# Tally_v03.net
KiCad netlist of a schematic drawn in EAGLE
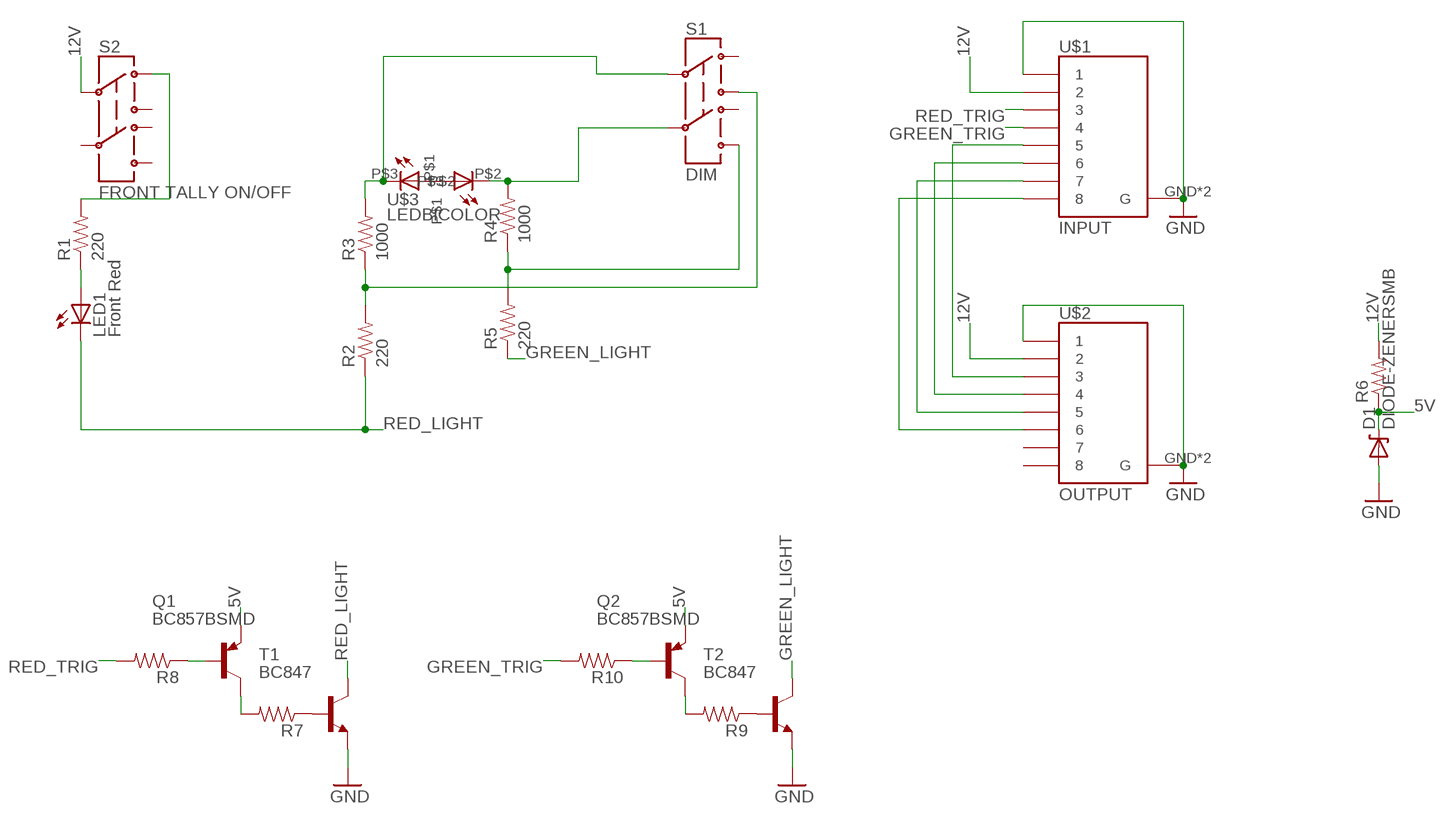
[diagram p0: schematic, sheet 1]

(export (version "E")
  (design (tool "Eeschema 10.0.6"))
  (components
    (comp (ref "D1")
      (value "DIODE-ZENERSMB")
      (footprint "eagle-import:SMB-DIODE")
      (libsource (lib "eagle-import") (part "DIODE-ZENERSMB"))
    )
    (comp (ref "LED1")
      (value "Front Red")
      (footprint "eagle-import:LED20")
      (libsource (lib "eagle-import") (part "LED20"))
    )
    (comp (ref "Q1")
      (value "BC857BSMD")
      (footprint "eagle-import:SOT23-BEC")
      (libsource (lib "eagle-import") (part "BC857SMDB"))
    )
    (comp (ref "Q2")
      (value "BC857BSMD")
      (footprint "eagle-import:SOT23-BEC")
      (libsource (lib "eagle-import") (part "BC857SMDB"))
    )
    (comp (ref "R1")
      (value "220")
      (footprint "eagle-import:0603-RES")
      (libsource (lib "eagle-import") (part "RESISTOR0603-RES"))
    )
    (comp (ref "R2")
      (value "220")
      (footprint "eagle-import:0603-RES")
      (libsource (lib "eagle-import") (part "RESISTOR0603-RES"))
    )
    (comp (ref "R3")
      (value "1000")
      (footprint "eagle-import:0603-RES")
      (libsource (lib "eagle-import") (part "RESISTOR0603-RES"))
    )
    (comp (ref "R4")
      (value "1000")
      (footprint "eagle-import:0603-RES")
      (libsource (lib "eagle-import") (part "RESISTOR0603-RES"))
    )
    (comp (ref "R5")
      (value "220")
      (footprint "eagle-import:0603-RES")
      (libsource (lib "eagle-import") (part "RESISTOR0603-RES"))
    )
    (comp (ref "R6")
      (value "RESISTOR0603-RES")
      (footprint "eagle-import:0603-RES")
      (libsource (lib "eagle-import") (part "RESISTOR0603-RES"))
    )
    (comp (ref "R7")
      (value "RESISTOR0603-RES")
      (footprint "eagle-import:0603-RES")
      (libsource (lib "eagle-import") (part "RESISTOR0603-RES"))
    )
    (comp (ref "R8")
      (value "RESISTOR0603-RES")
      (footprint "eagle-import:0603-RES")
      (libsource (lib "eagle-import") (part "RESISTOR0603-RES"))
    )
    (comp (ref "R9")
      (value "RESISTOR0603-RES")
      (footprint "eagle-import:0603-RES")
      (libsource (lib "eagle-import") (part "RESISTOR0603-RES"))
    )
    (comp (ref "R10")
      (value "RESISTOR0603-RES")
      (footprint "eagle-import:0603-RES")
      (libsource (lib "eagle-import") (part "RESISTOR0603-RES"))
    )
    (comp (ref "S1")
      (value "DIM")
      (footprint "eagle-import:TECONNECTIVITY-DPDT")
      (libsource (lib "eagle-import") (part "SWITCH-DPDTPTH1"))
    )
    (comp (ref "S2")
      (value "FRONT TALLY ON/OFF")
      (footprint "eagle-import:TECONNECTIVITY-DPDT")
      (libsource (lib "eagle-import") (part "SWITCH-DPDTPTH1"))
    )
    (comp (ref "T1")
      (value "BC847")
      (footprint "eagle-import:SOT23")
      (libsource (lib "eagle-import") (part "BC847"))
    )
    (comp (ref "T2")
      (value "BC847")
      (footprint "eagle-import:SOT23")
      (libsource (lib "eagle-import") (part "BC847"))
    )
    (comp (ref "U$1")
      (value "INPUT")
      (footprint "eagle-import:RJ45-8_GND")
      (libsource (lib "eagle-import") (part "RJ45-8_GND"))
    )
    (comp (ref "U$2")
      (value "OUTPUT")
      (footprint "eagle-import:RJ45-8_GND")
      (libsource (lib "eagle-import") (part "RJ45-8_GND"))
    )
    (comp (ref "U$3")
      (value "LEDBICOLOR")
      (footprint "eagle-import:LEDBICOLOR")
      (libsource (lib "eagle-import") (part "LEDBICOLOR"))
    )
  )
  (nets
    (net (code "1") (name "/5V") (class "Default")
      (node (ref "D1") (pin "C") (pinfunction "C_C") (pintype "passive"))
      (node (ref "Q1") (pin "E") (pinfunction "E_E") (pintype "passive"))
      (node (ref "Q2") (pin "E") (pinfunction "E_E") (pintype "passive"))
      (node (ref "R6") (pin "1") (pinfunction "1_1") (pintype "passive"))
    )
    (net (code "2") (name "/12V") (class "Default")
      (node (ref "R6") (pin "2") (pinfunction "2_2") (pintype "passive"))
      (node (ref "S2") (pin "P$2") (pinfunction "2_P$2") (pintype "bidirectional"))
      (node (ref "U$1") (pin "2") (pinfunction "2_2") (pintype "bidirectional"))
      (node (ref "U$2") (pin "2") (pinfunction "2_2") (pintype "bidirectional"))
    )
    (net (code "3") (name "/GREEN_LIGHT") (class "Default")
      (node (ref "R5") (pin "1") (pinfunction "1_1") (pintype "passive"))
      (node (ref "T2") (pin "3") (pinfunction "C_3") (pintype "passive"))
    )
    (net (code "4") (name "/GREEN_TRIG") (class "Default")
      (node (ref "R10") (pin "2") (pinfunction "2_2") (pintype "passive"))
      (node (ref "U$1") (pin "4") (pinfunction "4_4") (pintype "bidirectional"))
    )
    (net (code "5") (name "/RED_LIGHT") (class "Default")
      (node (ref "LED1") (pin "P$2") (pinfunction "C_P$2") (pintype "passive"))
      (node (ref "R2") (pin "1") (pinfunction "1_1") (pintype "passive"))
      (node (ref "T1") (pin "3") (pinfunction "C_3") (pintype "passive"))
    )
    (net (code "6") (name "/RED_TRIG") (class "Default")
      (node (ref "R8") (pin "2") (pinfunction "2_2") (pintype "passive"))
      (node (ref "U$1") (pin "3") (pinfunction "3_3") (pintype "bidirectional"))
    )
    (net (code "7") (name "GND") (class "Default")
      (node (ref "D1") (pin "A") (pinfunction "A_A") (pintype "passive"))
      (node (ref "T1") (pin "2") (pinfunction "E_2") (pintype "passive"))
      (node (ref "T2") (pin "2") (pinfunction "E_2") (pintype "passive"))
      (node (ref "U$1") (pin "1") (pinfunction "1_1") (pintype "bidirectional"))
      (node (ref "U$1") (pin "GND") (pinfunction "G_GND") (pintype "power_in"))
      (node (ref "U$1") (pin "GND1") (pinfunction "G_GND1") (pintype "power_in"))
      (node (ref "U$2") (pin "1") (pinfunction "1_1") (pintype "bidirectional"))
      (node (ref "U$2") (pin "GND") (pinfunction "G_GND") (pintype "power_in"))
      (node (ref "U$2") (pin "GND1") (pinfunction "G_GND1") (pintype "power_in"))
    )
    (net (code "8") (name "Net-(LED1-A)") (class "Default")
      (node (ref "LED1") (pin "P$1") (pinfunction "A_P$1") (pintype "passive"))
      (node (ref "R1") (pin "1") (pinfunction "1_1") (pintype "passive"))
    )
    (net (code "9") (name "Net-(Q1-PadB)") (class "Default")
      (node (ref "Q1") (pin "B") (pinfunction "B_B") (pintype "passive"))
      (node (ref "R8") (pin "1") (pinfunction "1_1") (pintype "passive"))
    )
    (net (code "10") (name "Net-(Q1-PadC)") (class "Default")
      (node (ref "Q1") (pin "C") (pinfunction "C_C") (pintype "passive"))
      (node (ref "R7") (pin "2") (pinfunction "2_2") (pintype "passive"))
    )
    (net (code "11") (name "Net-(Q2-PadB)") (class "Default")
      (node (ref "Q2") (pin "B") (pinfunction "B_B") (pintype "passive"))
      (node (ref "R10") (pin "1") (pinfunction "1_1") (pintype "passive"))
    )
    (net (code "12") (name "Net-(Q2-PadC)") (class "Default")
      (node (ref "Q2") (pin "C") (pinfunction "C_C") (pintype "passive"))
      (node (ref "R9") (pin "2") (pinfunction "2_2") (pintype "passive"))
    )
    (net (code "13") (name "Net-(S1-2)") (class "Default")
      (node (ref "R3") (pin "2") (pinfunction "2_2") (pintype "passive"))
      (node (ref "S1") (pin "P$2") (pinfunction "2_P$2") (pintype "bidirectional"))
      (node (ref "U$3") (pin "P$3") (pinfunction "P$3_P$3") (pintype "bidirectional"))
    )
    (net (code "14") (name "Net-(S1-3)") (class "Default")
      (node (ref "R2") (pin "2") (pinfunction "2_2") (pintype "passive"))
      (node (ref "R3") (pin "1") (pinfunction "1_1") (pintype "passive"))
      (node (ref "S1") (pin "P$3") (pinfunction "3_P$3") (pintype "bidirectional"))
    )
    (net (code "15") (name "Net-(S1-5)") (class "Default")
      (node (ref "R4") (pin "2") (pinfunction "2_2") (pintype "passive"))
      (node (ref "S1") (pin "P$5") (pinfunction "5_P$5") (pintype "bidirectional"))
      (node (ref "U$3") (pin "P$2") (pinfunction "P$2_P$2") (pintype "bidirectional"))
    )
    (net (code "16") (name "Net-(S1-6)") (class "Default")
      (node (ref "R4") (pin "1") (pinfunction "1_1") (pintype "passive"))
      (node (ref "R5") (pin "2") (pinfunction "2_2") (pintype "passive"))
      (node (ref "S1") (pin "P$6") (pinfunction "6_P$6") (pintype "bidirectional"))
    )
    (net (code "17") (name "Net-(S2-1)") (class "Default")
      (node (ref "R1") (pin "2") (pinfunction "2_2") (pintype "passive"))
      (node (ref "S2") (pin "P$1") (pinfunction "1_P$1") (pintype "bidirectional"))
    )
    (net (code "18") (name "Net-(T1-B)") (class "Default")
      (node (ref "R7") (pin "1") (pinfunction "1_1") (pintype "passive"))
      (node (ref "T1") (pin "1") (pinfunction "B_1") (pintype "passive"))
    )
    (net (code "19") (name "Net-(T2-B)") (class "Default")
      (node (ref "R9") (pin "1") (pinfunction "1_1") (pintype "passive"))
      (node (ref "T2") (pin "1") (pinfunction "B_1") (pintype "passive"))
    )
    (net (code "20") (name "Net-(U$1-Pad5)") (class "Default")
      (node (ref "U$1") (pin "5") (pinfunction "5_5") (pintype "bidirectional"))
      (node (ref "U$2") (pin "3") (pinfunction "3_3") (pintype "bidirectional"))
    )
    (net (code "21") (name "Net-(U$1-Pad6)") (class "Default")
      (node (ref "U$1") (pin "6") (pinfunction "6_6") (pintype "bidirectional"))
      (node (ref "U$2") (pin "4") (pinfunction "4_4") (pintype "bidirectional"))
    )
    (net (code "22") (name "Net-(U$1-Pad7)") (class "Default")
      (node (ref "U$1") (pin "7") (pinfunction "7_7") (pintype "bidirectional"))
      (node (ref "U$2") (pin "5") (pinfunction "5_5") (pintype "bidirectional"))
    )
    (net (code "23") (name "Net-(U$1-Pad8)") (class "Default")
      (node (ref "U$1") (pin "8") (pinfunction "8_8") (pintype "bidirectional"))
      (node (ref "U$2") (pin "6") (pinfunction "6_6") (pintype "bidirectional"))
    )
    (net (code "24") (name "unconnected-(S1-1-PadP$1)") (class "Default")
      (node (ref "S1") (pin "P$1") (pinfunction "1_P$1") (pintype "bidirectional"))
    )
    (net (code "25") (name "unconnected-(S1-4-PadP$4)") (class "Default")
      (node (ref "S1") (pin "P$4") (pinfunction "4_P$4") (pintype "bidirectional"))
    )
    (net (code "26") (name "unconnected-(S2-3-PadP$3)") (class "Default")
      (node (ref "S2") (pin "P$3") (pinfunction "3_P$3") (pintype "bidirectional"))
    )
    (net (code "27") (name "unconnected-(S2-4-PadP$4)") (class "Default")
      (node (ref "S2") (pin "P$4") (pinfunction "4_P$4") (pintype "bidirectional"))
    )
    (net (code "28") (name "unconnected-(S2-5-PadP$5)") (class "Default")
      (node (ref "S2") (pin "P$5") (pinfunction "5_P$5") (pintype "bidirectional"))
    )
    (net (code "29") (name "unconnected-(S2-6-PadP$6)") (class "Default")
      (node (ref "S2") (pin "P$6") (pinfunction "6_P$6") (pintype "bidirectional"))
    )
    (net (code "30") (name "unconnected-(U$2-Pad7)") (class "Default")
      (node (ref "U$2") (pin "7") (pinfunction "7_7") (pintype "bidirectional"))
    )
    (net (code "31") (name "unconnected-(U$2-Pad8)") (class "Default")
      (node (ref "U$2") (pin "8") (pinfunction "8_8") (pintype "bidirectional"))
    )
    (net (code "32") (name "unconnected-(U$3-PadP$1)") (class "Default")
      (node (ref "U$3") (pin "P$1") (pinfunction "P$1_P$1") (pintype "bidirectional"))
    )
  )
)
